# TIDA-01592_Power_Supply1.net
KiCad netlist of a schematic drawn in Altium Designer
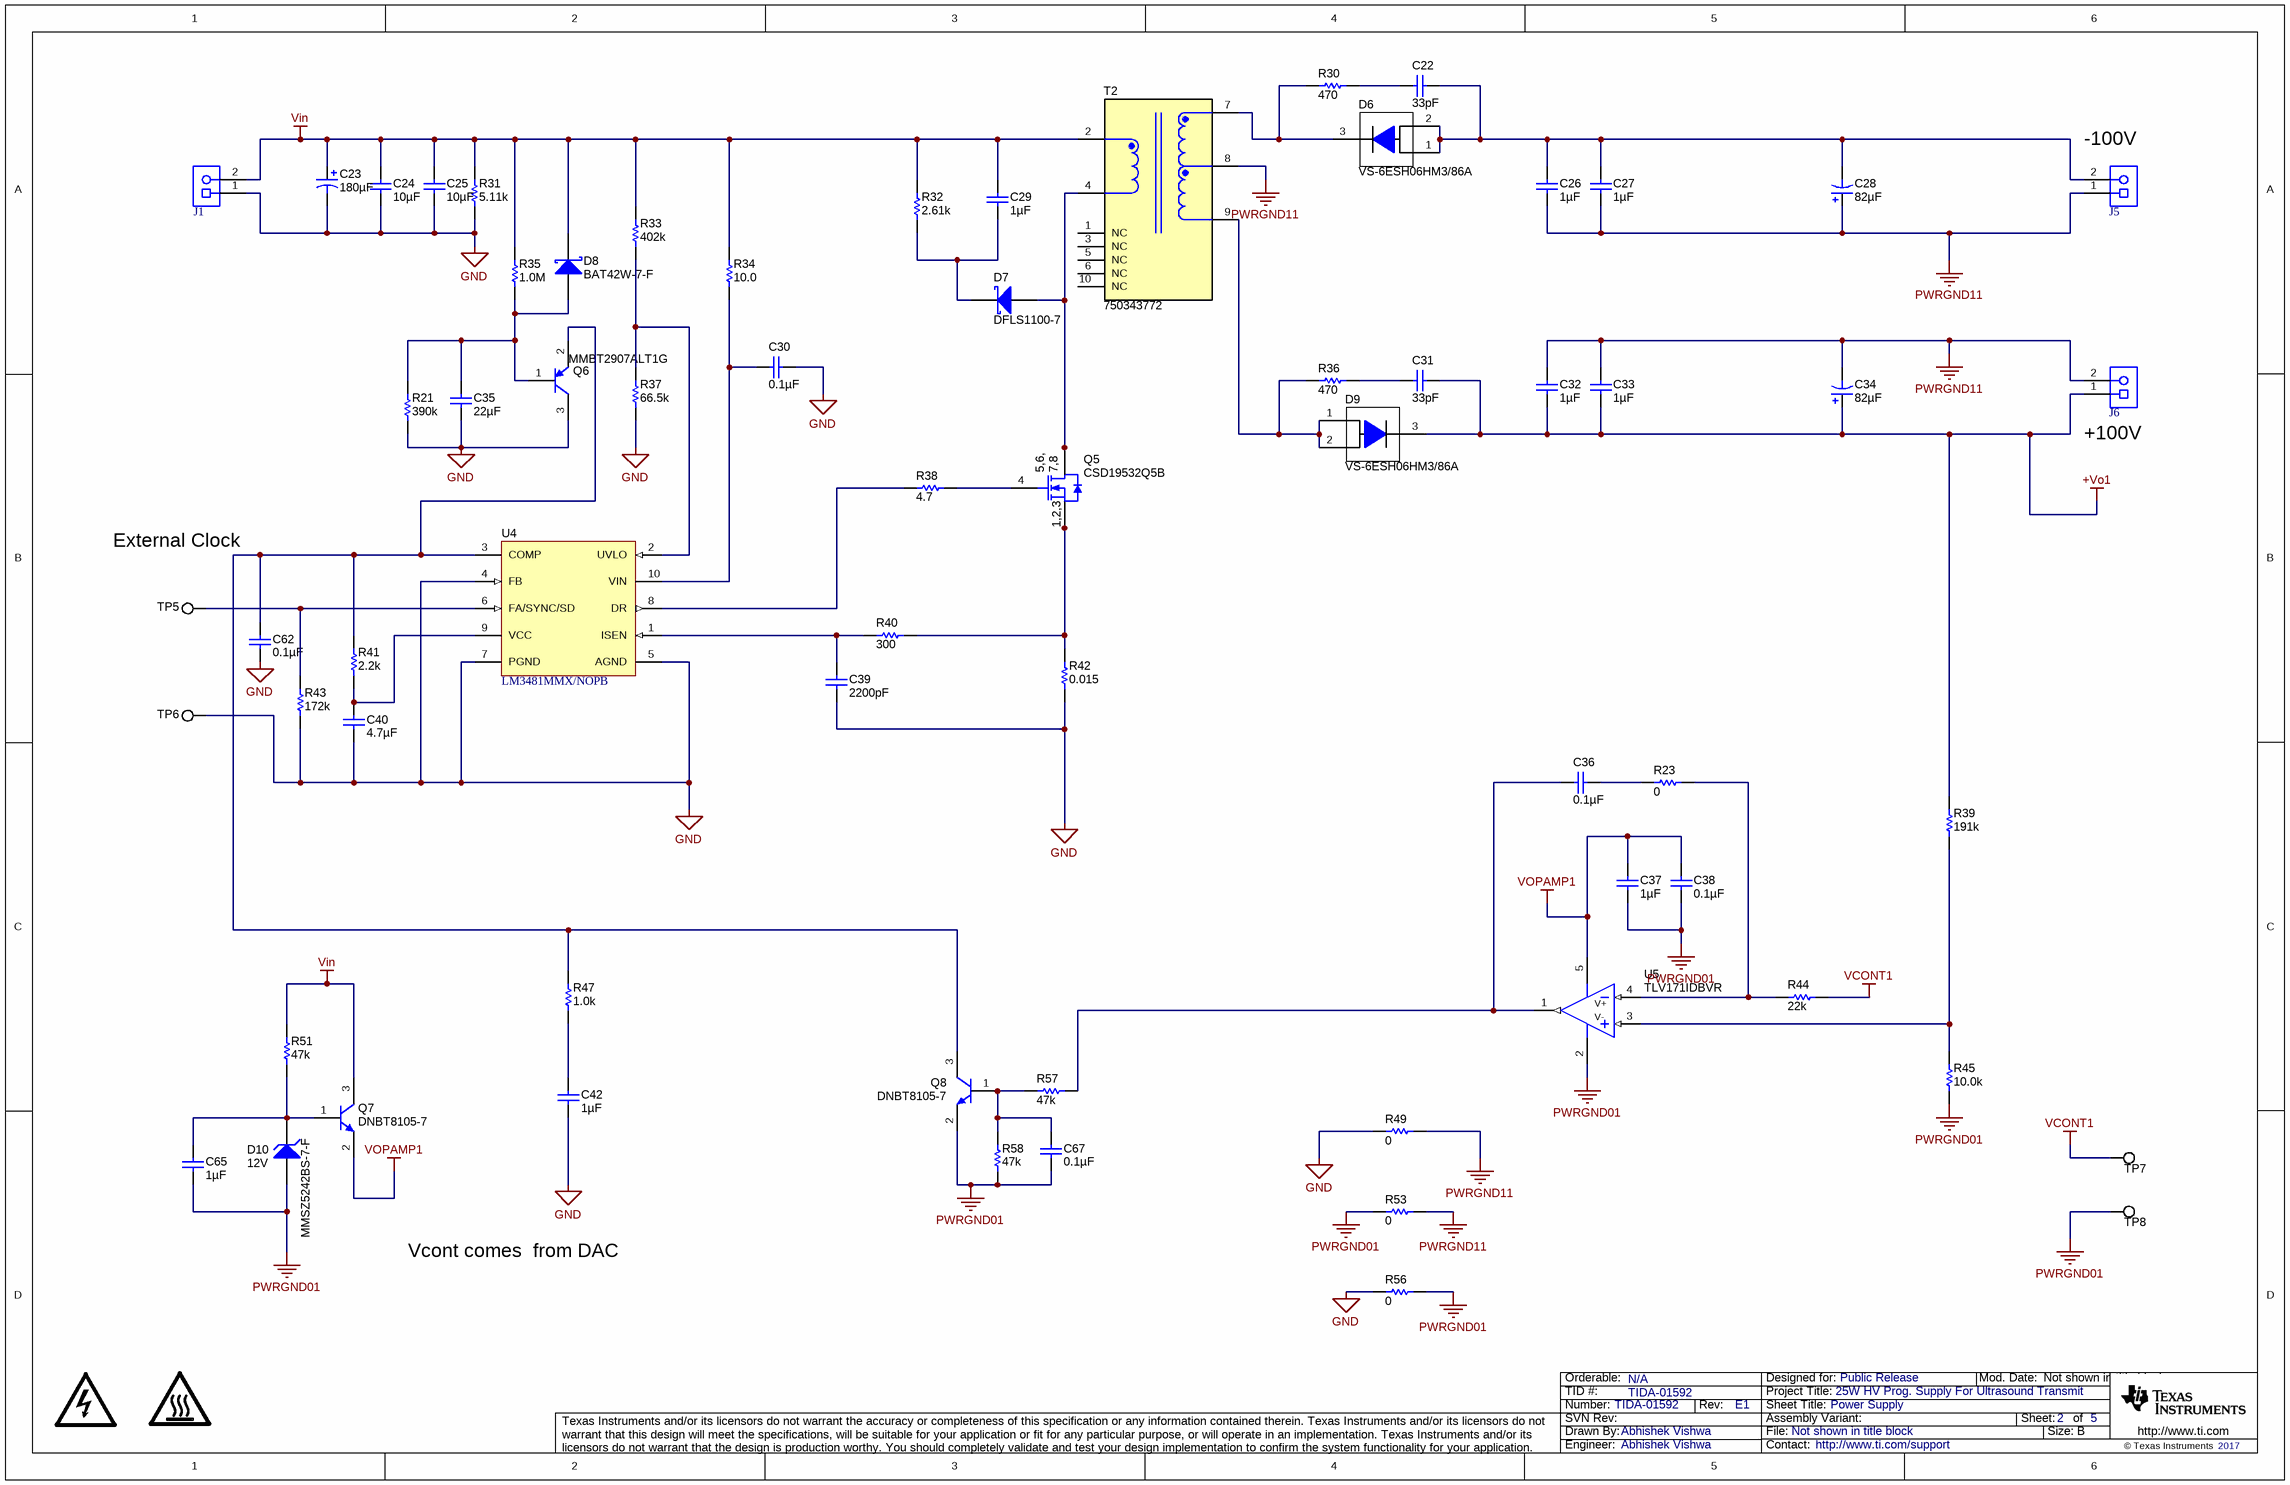
[diagram p0: TIDA-01592_Power Supply1.SchDoc]

(export (version "E")
  (design (tool "Eeschema 10.0.6"))
  (components
    (comp (ref "C22")
      (value "12067A330JAT2A")
      (footprint "1206")
      (description "CAP, CERM, 33 pF, 500 V,+/- 5%, C0G/NP0, 1206")
      (fields
        (field (name "VALUEDISPLAYED") "33pF")
        (field (name "MANUFACTURER") "AVX")
        (field (name "PUBLISHER") "Texas Instruments")
      )
      (libsource (lib "Capacitor_Ceramic") (part "12067A330JAT2A"))
    )
    (comp (ref "C23")
      (value "35TXW180MEFC6.3X25")
      (footprint "FC_630x1120")
      (description "CAP, AL, 180 µF, 35 V, +/- 20%, TH")
      (fields
        (field (name "VALUEDISPLAYED") "180µF")
        (field (name "MANUFACTURER") "Rubycon")
        (field (name "PUBLISHER") "Texas Instruments")
      )
      (libsource (lib "Capacitor_Aluminum") (part "EEU-FC1V470"))
    )
    (comp (ref "C24")
      (value "GRM31CR61H106KA12L")
      (footprint "1206_180")
      (description "CAP, CERM, 10 µF, 50 V,+/- 10%, X5R, 1206")
      (fields
        (field (name "VALUEDISPLAYED") "10µF")
        (field (name "MANUFACTURER") "MuRata")
        (field (name "PUBLISHER") "Texas Instruments")
      )
      (libsource (lib "Capacitor_Ceramic") (part "GRM31CR61H106KA12L"))
    )
    (comp (ref "C25")
      (value "GRM31CR61H106KA12L")
      (footprint "1206_180")
      (description "CAP, CERM, 10 µF, 50 V,+/- 10%, X5R, 1206")
      (fields
        (field (name "VALUEDISPLAYED") "10µF")
        (field (name "MANUFACTURER") "MuRata")
        (field (name "PUBLISHER") "Texas Instruments")
      )
      (libsource (lib "Capacitor_Ceramic") (part "GRM31CR61H106KA12L"))
    )
    (comp (ref "C26")
      (value "C4532X7T2E105M250KE")
      (footprint "1812_180")
      (description "CAP, CERM, 1 µF, 250 V,+/- 20%, X7T, 1812")
      (fields
        (field (name "VALUEDISPLAYED") "1µF")
        (field (name "MANUFACTURER") "TDK Corporation")
        (field (name "PUBLISHER") "Texas Instruments")
      )
      (libsource (lib "Capacitor_Ceramic") (part "C4532X7R1H105K160KA"))
    )
    (comp (ref "C27")
      (value "C4532X7T2E105M250KE")
      (footprint "1812_180")
      (description "CAP, CERM, 1 µF, 250 V,+/- 20%, X7T, 1812")
      (fields
        (field (name "VALUEDISPLAYED") "1µF")
        (field (name "MANUFACTURER") "TDK Corporation")
        (field (name "PUBLISHER") "Texas Instruments")
      )
      (libsource (lib "Capacitor_Ceramic") (part "C4532X7R1H105K160KA"))
    )
    (comp (ref "C28")
      (value "UCY2C820MPD9")
      (footprint "NHG_1000x2000")
      (description "CAP, AL, 82 µF, 160 V, +/- 20%, TH")
      (fields
        (field (name "VALUEDISPLAYED") "82µF")
        (field (name "MANUFACTURER") "Nichicon")
        (field (name "PUBLISHER") "Texas Instruments")
      )
      (libsource (lib "Capacitor_Aluminum") (part "ECA-2AHG101"))
    )
    (comp (ref "C29")
      (value "GRM31CR72A105KA01L")
      (footprint "1206_180")
      (description "CAP, CERM, 1 µF, 100 V,+/- 10%, X7R, 1206")
      (fields
        (field (name "VALUEDISPLAYED") "1µF")
        (field (name "MANUFACTURER") "MuRata")
        (field (name "PUBLISHER") "Texas Instruments")
      )
      (libsource (lib "Capacitor_Ceramic") (part "GRM31CR72A105KA01L"))
    )
    (comp (ref "C30")
      (value "GRM188R71H104KA93D")
      (footprint "0603")
      (description "CAP, CERM, 0.1 µF, 50 V,+/- 10%, X7R, 0603")
      (fields
        (field (name "VALUEDISPLAYED") "0.1µF")
        (field (name "MANUFACTURER") "MuRata")
        (field (name "PUBLISHER") "Texas Instruments")
      )
      (libsource (lib "Capacitor_Ceramic") (part "GRM188R71H104KA93D"))
    )
    (comp (ref "C31")
      (value "12067A330JAT2A")
      (footprint "1206")
      (description "CAP, CERM, 33 pF, 500 V,+/- 5%, C0G/NP0, 1206")
      (fields
        (field (name "VALUEDISPLAYED") "33pF")
        (field (name "MANUFACTURER") "AVX")
        (field (name "PUBLISHER") "Texas Instruments")
      )
      (libsource (lib "Capacitor_Ceramic") (part "12067A330JAT2A"))
    )
    (comp (ref "C32")
      (value "C4532X7T2E105M250KE")
      (footprint "1812_180")
      (description "CAP, CERM, 1 µF, 250 V,+/- 20%, X7T, 1812")
      (fields
        (field (name "VALUEDISPLAYED") "1µF")
        (field (name "MANUFACTURER") "TDK Corporation")
        (field (name "PUBLISHER") "Texas Instruments")
      )
      (libsource (lib "Capacitor_Ceramic") (part "C4532X7R1H105K160KA"))
    )
    (comp (ref "C33")
      (value "C4532X7T2E105M250KE")
      (footprint "1812_180")
      (description "CAP, CERM, 1 µF, 250 V,+/- 20%, X7T, 1812")
      (fields
        (field (name "VALUEDISPLAYED") "1µF")
        (field (name "MANUFACTURER") "TDK Corporation")
        (field (name "PUBLISHER") "Texas Instruments")
      )
      (libsource (lib "Capacitor_Ceramic") (part "C4532X7R1H105K160KA"))
    )
    (comp (ref "C34")
      (value "UCY2C820MPD9")
      (footprint "NHG_1000x2000")
      (description "CAP, AL, 82 µF, 160 V, +/- 20%, TH")
      (fields
        (field (name "VALUEDISPLAYED") "82µF")
        (field (name "MANUFACTURER") "Nichicon")
        (field (name "PUBLISHER") "Texas Instruments")
      )
      (libsource (lib "Capacitor_Aluminum") (part "ECA-2AHG101"))
    )
    (comp (ref "C35")
      (value "C2012X5R1V226M125AC")
      (footprint "0805_HV1")
      (description "CAP, CERM, 22 µF, 35 V,+/- 20%, X5R, 0805")
      (fields
        (field (name "VALUEDISPLAYED") "22µF")
        (field (name "MANUFACTURER") "TDK Corporation")
        (field (name "PUBLISHER") "Texas Instruments")
      )
      (libsource (lib "Capacitor_Ceramic") (part "GRM21BC81C226ME44L"))
    )
    (comp (ref "C36")
      (value "GRM188R71H104KA93D")
      (footprint "0603")
      (description "CAP, CERM, 0.1 µF, 50 V,+/- 10%, X7R, 0603")
      (fields
        (field (name "VALUEDISPLAYED") "0.1µF")
        (field (name "MANUFACTURER") "MuRata")
        (field (name "PUBLISHER") "Texas Instruments")
      )
      (libsource (lib "Capacitor_Ceramic") (part "GRM188R71H104KA93D"))
    )
    (comp (ref "C37")
      (value "UMK107AB7105KA-T")
      (footprint "0603")
      (description "CAP, CERM, 1 µF, 50 V,+/- 10%, X7R, 0603")
      (fields
        (field (name "VALUEDISPLAYED") "1µF")
        (field (name "MANUFACTURER") "Taiyo Yuden")
        (field (name "PUBLISHER") "Texas Instruments")
      )
      (libsource (lib "Capacitor_Ceramic") (part "UMK107AB7105KA-T"))
    )
    (comp (ref "C38")
      (value "GRM188R71H104KA93D")
      (footprint "0603")
      (description "CAP, CERM, 0.1 µF, 50 V,+/- 10%, X7R, 0603")
      (fields
        (field (name "VALUEDISPLAYED") "0.1µF")
        (field (name "MANUFACTURER") "MuRata")
        (field (name "PUBLISHER") "Texas Instruments")
      )
      (libsource (lib "Capacitor_Ceramic") (part "GRM188R71H104KA93D"))
    )
    (comp (ref "C39")
      (value "GRM155R61H222KA01D")
      (footprint "0402")
      (description "CAP, CERM, 2200 pF, 50 V,+/- 10%, X5R, 0402")
      (fields
        (field (name "VALUEDISPLAYED") "2200pF")
        (field (name "MANUFACTURER") "MuRata")
        (field (name "PUBLISHER") "Texas Instruments")
      )
      (libsource (lib "Capacitor_Ceramic") (part "GRM155R61H222KA01D"))
    )
    (comp (ref "C40")
      (value "0603ZD475KAT2A")
      (footprint "0603")
      (description "CAP, CERM, 4.7 µF, 10 V,+/- 10%, X5R, 0603")
      (fields
        (field (name "VALUEDISPLAYED") "4.7µF")
        (field (name "MANUFACTURER") "AVX")
        (field (name "PUBLISHER") "Texas Instruments")
      )
      (libsource (lib "Capacitor_Ceramic") (part "0603ZD475KAT2A"))
    )
    (comp (ref "C42")
      (value "C0603C105K3RACTU")
      (footprint "0603")
      (description "CAP, CERM, 1 µF, 25 V,+/- 10%, X7R, 0603")
      (fields
        (field (name "VALUEDISPLAYED") "1µF")
        (field (name "MANUFACTURER") "Kemet")
        (field (name "PUBLISHER") "Texas Instruments")
      )
      (libsource (lib "Capacitor_Ceramic") (part "C0603C105K3RACTU"))
    )
    (comp (ref "C62")
      (value "GRM188R71H104KA93D")
      (footprint "0603")
      (description "CAP, CERM, 0.1 µF, 50 V,+/- 10%, X7R, 0603")
      (fields
        (field (name "VALUEDISPLAYED") "0.1µF")
        (field (name "MANUFACTURER") "MuRata")
        (field (name "PUBLISHER") "Texas Instruments")
      )
      (libsource (lib "Capacitor_Ceramic") (part "GRM188R71H104KA93D"))
    )
    (comp (ref "C65")
      (value "C0603C105K3RACTU")
      (footprint "0603")
      (description "CAP, CERM, 1 µF, 25 V,+/- 10%, X7R, 0603")
      (fields
        (field (name "VALUEDISPLAYED") "1µF")
        (field (name "MANUFACTURER") "Kemet")
        (field (name "PUBLISHER") "Texas Instruments")
      )
      (libsource (lib "Capacitor_Ceramic") (part "C0603C105K3RACTU"))
    )
    (comp (ref "C67")
      (value "GRM188R71H104KA93D")
      (footprint "0603")
      (description "CAP, CERM, 0.1 µF, 50 V,+/- 10%, X7R, 0603")
      (fields
        (field (name "VALUEDISPLAYED") "0.1µF")
        (field (name "MANUFACTURER") "MuRata")
        (field (name "PUBLISHER") "Texas Instruments")
      )
      (libsource (lib "Capacitor_Ceramic") (part "GRM188R71H104KA93D"))
    )
    (comp (ref "D6")
      (value "VS-6ESH06HM3/86A")
      (footprint "TO-277A")
      (description "Diode, Hyperfast, 600 V, 6 A, AEC-Q101, TO-277A")
      (fields
        (field (name "MANUFACTURER") "Vishay-Semiconductor")
        (field (name "SYMBOLCREATOR") "a0412235")
        (field (name "PUBLISHER") "Texas Instruments")
      )
      (libsource (lib "Diode") (part "VS-6ESH06HM3/86A"))
    )
    (comp (ref "D7")
      (value "DFLS1100-7")
      (footprint "PowerDI123")
      (description "Diode, Schottky, 100 V, 1 A, PowerDI123")
      (fields (field (name "MANUFACTURER") "Diodes Inc.") (field (name "PUBLISHER") "Texas Instruments"))
      (libsource (lib "Diode") (part "DFLS1100-7"))
    )
    (comp (ref "D8")
      (value "BAT42W-7-F")
      (footprint "SOD-123")
      (description "Diode, Schottky, 30 V, 0.2 A, SOD-123")
      (fields (field (name "MANUFACTURER") "Diodes Inc.") (field (name "PUBLISHER") "Texas Instruments"))
      (libsource (lib "Diode") (part "BAT42W-7-F"))
    )
    (comp (ref "D9")
      (value "VS-6ESH06HM3/86A")
      (footprint "TO-277A")
      (description "Diode, Hyperfast, 600 V, 6 A, AEC-Q101, TO-277A")
      (fields
        (field (name "MANUFACTURER") "Vishay-Semiconductor")
        (field (name "SYMBOLCREATOR") "a0412235")
        (field (name "PUBLISHER") "Texas Instruments")
      )
      (libsource (lib "") (part "VS-6ESH06HM3/86A_1"))
    )
    (comp (ref "D10")
      (value "MMSZ5242BS-7-F")
      (footprint "SOD-323")
      (description "Diode, Zener, 12 V, 200 mW, SOD-323")
      (fields
        (field (name "ALTIUM_VALUE") "12V")
        (field (name "MANUFACTURER") "Diodes Inc.")
        (field (name "SYMBOLCREATOR") "a0412235")
        (field (name "PUBLISHER") "Texas Instruments")
      )
      (libsource (lib "ZenerDiodes") (part "MMSZ5242BS-7-F"))
    )
    (comp (ref "J1")
      (value "1727010")
      (footprint "PhoenixConact_1727010")
      (description "Conn Term Block, 2POS, 3.81mm, TH")
      (fields
        (field (name "MANUFACTURER") "Phoenix Contact")
        (field (name "SYMBOLCREATOR") "a0412235")
        (field (name "PUBLISHER") "Texas Instruments")
      )
      (libsource (lib "Connectors_Phoenix_Contact") (part "1727010"))
    )
    (comp (ref "J5")
      (value "1727010")
      (footprint "PhoenixConact_1727010")
      (description "Conn Term Block, 2POS, 3.81mm, TH")
      (fields
        (field (name "MANUFACTURER") "Phoenix Contact")
        (field (name "SYMBOLCREATOR") "a0412235")
        (field (name "PUBLISHER") "Texas Instruments")
      )
      (libsource (lib "") (part "1727010_1"))
    )
    (comp (ref "J6")
      (value "1727010")
      (footprint "PhoenixConact_1727010")
      (description "Conn Term Block, 2POS, 3.81mm, TH")
      (fields
        (field (name "MANUFACTURER") "Phoenix Contact")
        (field (name "SYMBOLCREATOR") "a0412235")
        (field (name "PUBLISHER") "Texas Instruments")
      )
      (libsource (lib "") (part "1727010_1"))
    )
    (comp (ref "Q5")
      (value "CSD19532Q5B")
      (footprint "DNK0008A")
      (description "MOSFET, N-CH, 100 V, 17 A, DNK0008A (VSON-CLIP-8)")
      (fields
        (field (name "MANUFACTURER") "Texas Instruments")
        (field (name "PUBLISHER") "Texas Instruments")
      )
      (libsource (lib "FETs") (part "CSD19532Q5B"))
    )
    (comp (ref "Q6")
      (value "MMBT2907ALT1G")
      (footprint "SOT-23")
      (description "Transistor, PNP, 60 V, 0.6 A, SOT-23")
      (fields (field (name "MANUFACTURER") "ON Semiconductor") (field (name "PUBLISHER") "Texas Instruments"))
      (libsource (lib "Bipolar_Transistor") (part "MMBT2907ALT1G, ON Semiconductor"))
    )
    (comp (ref "Q7")
      (value "DNBT8105-7")
      (footprint "SOT-23")
      (description "Transistor, NPN, 60 V, 1 A, AEC-Q101, SOT-23")
      (fields (field (name "MANUFACTURER") "Diodes Inc.") (field (name "PUBLISHER") "Texas Instruments"))
      (libsource (lib "Bipolar_Transistor") (part "DNBT8105-7, Diodes Inc."))
    )
    (comp (ref "Q8")
      (value "DNBT8105-7")
      (footprint "SOT-23")
      (description "Transistor, NPN, 60 V, 1 A, AEC-Q101, SOT-23")
      (fields (field (name "MANUFACTURER") "Diodes Inc.") (field (name "PUBLISHER") "Texas Instruments"))
      (libsource (lib "Bipolar_Transistor") (part "DNBT8105-7, Diodes Inc."))
    )
    (comp (ref "R21")
      (value "CRCW0603390KJNEA")
      (footprint "0603")
      (description "RES, 390 k, 5%, 0.1 W, 0603")
      (fields
        (field (name "VALUEDISPLAYED") "390k")
        (field (name "MANUFACTURER") "Vishay-Dale")
        (field (name "PUBLISHER") "Texas Instruments")
      )
      (libsource (lib "Resistor_0603") (part "CRCW0603390KJNEA"))
    )
    (comp (ref "R23")
      (value "CRCW04020000Z0ED")
      (footprint "0402")
      (description "RES, 0, 5%, 0.063 W, 0402")
      (fields
        (field (name "VALUEDISPLAYED") "0")
        (field (name "MANUFACTURER") "Vishay-Dale")
        (field (name "PUBLISHER") "Texas Instruments")
      )
      (libsource (lib "Resistor_0402") (part "CRCW04020000Z0ED"))
    )
    (comp (ref "R30")
      (value "CRCW1206470RJNEA")
      (footprint "1206")
      (description "RES, 470, 5%, 0.25 W, 1206")
      (fields
        (field (name "VALUEDISPLAYED") "470")
        (field (name "MANUFACTURER") "Vishay-Dale")
        (field (name "PUBLISHER") "Texas Instruments")
      )
      (libsource (lib "Resistor_1206") (part "CRCW1206470RJNEA"))
    )
    (comp (ref "R31")
      (value "TNPW06035K11BEEA")
      (footprint "TNPW0603")
      (description "RES, 5.11 k, 0.1%, 0.1 W, AEC-Q200 Grade 1, 0603")
      (fields
        (field (name "VALUEDISPLAYED") "5.11k")
        (field (name "MANUFACTURER") "Vishay-Dale")
        (field (name "PUBLISHER") "Texas Instruments")
      )
      (libsource (lib "Resistor_0603") (part "TNPW06035K11BEEA"))
    )
    (comp (ref "R32")
      (value "CRCW20102K61FKEF")
      (footprint "2010")
      (description "RES, 2.61 k, 1%, 0.75 W, AEC-Q200 Grade 0, 2010")
      (fields
        (field (name "VALUEDISPLAYED") "2.61k")
        (field (name "MANUFACTURER") "Vishay-Dale")
        (field (name "PUBLISHER") "Texas Instruments")
      )
      (libsource (lib "Resistor_2010") (part "CRCW20102K61FKEF"))
    )
    (comp (ref "R33")
      (value "CRCW0603402KFKEA")
      (footprint "0603")
      (description "RES, 402 k, 1%, 0.1 W, 0603")
      (fields
        (field (name "VALUEDISPLAYED") "402k")
        (field (name "MANUFACTURER") "Vishay-Dale")
        (field (name "PUBLISHER") "Texas Instruments")
      )
      (libsource (lib "Resistor_0603") (part "CRCW0603402KFKEA"))
    )
    (comp (ref "R34")
      (value "CRCW060310R0FKEAHP")
      (footprint "0603")
      (description "RES, 10.0, 1%, 0.25 W, 0603")
      (fields
        (field (name "R4") "10.0")
        (field (name "MANUFACTURER") "Vishay-Dale")
        (field (name "PUBLISHER") "Texas Instruments")
      )
      (libsource (lib "Resistor_0603") (part "CRCW060310R0FKEAHP"))
    )
    (comp (ref "R35")
      (value "CRCW06031M00JNEA")
      (footprint "0603")
      (description "RES, 1.0 M, 5%, 0.1 W, 0603")
      (fields
        (field (name "VALUEDISPLAYED") "1.0M")
        (field (name "MANUFACTURER") "Vishay-Dale")
        (field (name "PUBLISHER") "Texas Instruments")
      )
      (libsource (lib "Resistor_0603") (part "CRCW06031M00JNEA"))
    )
    (comp (ref "R36")
      (value "CRCW1206470RJNEA")
      (footprint "1206")
      (description "RES, 470, 5%, 0.25 W, 1206")
      (fields
        (field (name "VALUEDISPLAYED") "470")
        (field (name "MANUFACTURER") "Vishay-Dale")
        (field (name "PUBLISHER") "Texas Instruments")
      )
      (libsource (lib "Resistor_1206") (part "CRCW1206470RJNEA"))
    )
    (comp (ref "R37")
      (value "CRCW060366K5FKEA")
      (footprint "0603")
      (description "RES, 66.5 k, 1%, 0.1 W, 0603")
      (fields
        (field (name "VALUEDISPLAYED") "66.5k")
        (field (name "MANUFACTURER") "Vishay-Dale")
        (field (name "PUBLISHER") "Texas Instruments")
      )
      (libsource (lib "Resistor_0603") (part "CRCW060366K5FKEA"))
    )
    (comp (ref "R38")
      (value "CRCW06034R70JNEA")
      (footprint "0603")
      (description "RES, 4.7, 5%, 0.1 W, 0603")
      (fields
        (field (name "VALUEDISPLAYED") "4.7")
        (field (name "MANUFACTURER") "Vishay-Dale")
        (field (name "PUBLISHER") "Texas Instruments")
      )
      (libsource (lib "Resistor_0603") (part "CRCW06034R70JNEA"))
    )
    (comp (ref "R39")
      (value "CRCW0603191KFKEA")
      (footprint "0603")
      (description "RES, 191 k, 1%, 0.1 W, 0603")
      (fields
        (field (name "VALUEDISPLAYED") "191k")
        (field (name "MANUFACTURER") "Vishay-Dale")
        (field (name "PUBLISHER") "Texas Instruments")
      )
      (libsource (lib "Resistor_0603") (part "CRCW0603191KFKEA"))
    )
    (comp (ref "R40")
      (value "CRCW0603300RJNEA")
      (footprint "0603")
      (description "RES, 300, 5%, 0.1 W, 0603")
      (fields
        (field (name "VALUEDISPLAYED") "300")
        (field (name "MANUFACTURER") "Vishay-Dale")
        (field (name "PUBLISHER") "Texas Instruments")
      )
      (libsource (lib "Resistor_0603") (part "CRCW0603300RJNEA"))
    )
    (comp (ref "R41")
      (value "ERJ-3GEYJ222V")
      (footprint "0603")
      (description "RES, 2.2 k, 5%, 0.1 W, AEC-Q200 Grade 0, 0603")
      (fields
        (field (name "VALUEDISPLAYED") "2.2k")
        (field (name "MANUFACTURER") "Panasonic")
        (field (name "PUBLISHER") "Texas Instruments")
      )
      (libsource (lib "Resistor_0603") (part "ERJ-3GEYJ222V"))
    )
    (comp (ref "R42")
      (value "WSL2010R0150FEA18")
      (footprint "2010")
      (description "RES, 0.015, 1%, 1 W, 2010")
      (fields
        (field (name "VALUEDISPLAYED") "0.015")
        (field (name "MANUFACTURER") "Vishay-Dale")
        (field (name "PUBLISHER") "Texas Instruments")
      )
      (libsource (lib "Resistor_2010") (part "WSL2010R0150FEA18"))
    )
    (comp (ref "R43")
      (value "RT0603DRE07172KL")
      (footprint "0603")
      (description "RES, 172 k, 0.5%, 0.1 W, 0603")
      (fields
        (field (name "VALUEDISPLAYED") "172k")
        (field (name "MANUFACTURER") "Yageo America")
        (field (name "PUBLISHER") "Texas Instruments")
      )
      (libsource (lib "Resistor_0603") (part "RT0603DRE07172KL"))
    )
    (comp (ref "R44")
      (value "CRCW060322K0JNEA")
      (footprint "0603")
      (description "RES, 22 k, 5%, 0.1 W, 0603")
      (fields
        (field (name "VALUEDISPLAYED") "22k")
        (field (name "MANUFACTURER") "Vishay-Dale")
        (field (name "PUBLISHER") "Texas Instruments")
      )
      (libsource (lib "Resistor_0603") (part "CRCW060322K0JNEA"))
    )
    (comp (ref "R45")
      (value "CRCW060310K0FKEA")
      (footprint "0603")
      (description "RES, 10.0 k, 1%, 0.1 W, 0603")
      (fields
        (field (name "VALUEDISPLAYED") "10.0k")
        (field (name "MANUFACTURER") "Vishay-Dale")
        (field (name "PUBLISHER") "Texas Instruments")
      )
      (libsource (lib "Resistor_0603") (part "CRCW060310K0FKEA"))
    )
    (comp (ref "R47")
      (value "CRCW06031K00JNEA")
      (footprint "0603")
      (description "RES, 1.0 k, 5%, 0.1 W, 0603")
      (fields
        (field (name "VALUEDISPLAYED") "1.0k")
        (field (name "MANUFACTURER") "Vishay-Dale")
        (field (name "PUBLISHER") "Texas Instruments")
      )
      (libsource (lib "Resistor_0603") (part "CRCW06031K00JNEA"))
    )
    (comp (ref "R49")
      (value "CRCW20100000Z0EF")
      (footprint "2010L")
      (description "RES, 0, 5%, 0.75 W, AEC-Q200 Grade 0, 2010")
      (fields
        (field (name "VALUEDISPLAYED") "0")
        (field (name "MANUFACTURER") "Vishay-Dale")
        (field (name "PUBLISHER") "Texas Instruments")
      )
      (libsource (lib "Resistor_2010") (part "CRCW20100000Z0EF"))
    )
    (comp (ref "R51")
      (value "CRCW120647K0JNEA")
      (footprint "1206")
      (description "RES, 47 k, 5%, 0.25 W, 1206")
      (fields
        (field (name "VALUEDISPLAYED") "47k")
        (field (name "MANUFACTURER") "Vishay-Dale")
        (field (name "PUBLISHER") "Texas Instruments")
      )
      (libsource (lib "Resistor_1206") (part "CRCW120647K0JNEA"))
    )
    (comp (ref "R53")
      (value "CRCW20100000Z0EF")
      (footprint "2010L")
      (description "RES, 0, 5%, 0.75 W, AEC-Q200 Grade 0, 2010")
      (fields
        (field (name "VALUEDISPLAYED") "0")
        (field (name "MANUFACTURER") "Vishay-Dale")
        (field (name "PUBLISHER") "Texas Instruments")
      )
      (libsource (lib "Resistor_2010") (part "CRCW20100000Z0EF"))
    )
    (comp (ref "R56")
      (value "CRCW20100000Z0EF")
      (footprint "2010L")
      (description "RES, 0, 5%, 0.75 W, AEC-Q200 Grade 0, 2010")
      (fields
        (field (name "VALUEDISPLAYED") "0")
        (field (name "MANUFACTURER") "Vishay-Dale")
        (field (name "PUBLISHER") "Texas Instruments")
      )
      (libsource (lib "Resistor_2010") (part "CRCW20100000Z0EF"))
    )
    (comp (ref "R57")
      (value "RC0603JR-0747KL")
      (footprint "0603")
      (description "RES, 47 k, 5%, 0.1 W, 0603")
      (fields
        (field (name "VALUEDISPLAYED") "47k")
        (field (name "MANUFACTURER") "Yageo America")
        (field (name "PUBLISHER") "Texas Instruments")
      )
      (libsource (lib "Resistor_0603") (part "RC0603JR-0747KL"))
    )
    (comp (ref "R58")
      (value "RC0603JR-0747KL")
      (footprint "0603")
      (description "RES, 47 k, 5%, 0.1 W, 0603")
      (fields
        (field (name "VALUEDISPLAYED") "47k")
        (field (name "MANUFACTURER") "Yageo America")
        (field (name "PUBLISHER") "Texas Instruments")
      )
      (libsource (lib "Resistor_0603") (part "RC0603JR-0747KL"))
    )
    (comp (ref "T2")
      (value "750343772")
      (footprint "Wurth_EE16_7_5_5278")
      (description "Transformer, 13 uH, TH")
      (fields (field (name "MANUFACTURER") "Wurth Elektronik"))
      (libsource (lib "Altium Vault - TI") (part "Wurth_750343772"))
    )
    (comp (ref "TP5")
      (value "5002")
      (footprint "Keystone5002")
      (description "Test Point, Miniature, White, TH")
      (fields (field (name "MANUFACTURER") "Keystone") (field (name "PUBLISHER") "Texas Instruments"))
      (libsource (lib "Connectors_Keystone") (part "5002"))
    )
    (comp (ref "TP6")
      (value "5002")
      (footprint "Keystone5002")
      (description "Test Point, Miniature, White, TH")
      (fields (field (name "MANUFACTURER") "Keystone") (field (name "PUBLISHER") "Texas Instruments"))
      (libsource (lib "Connectors_Keystone") (part "5002"))
    )
    (comp (ref "TP7")
      (value "5002")
      (footprint "Keystone5002")
      (description "Test Point, Miniature, White, TH")
      (fields (field (name "MANUFACTURER") "Keystone") (field (name "PUBLISHER") "Texas Instruments"))
      (libsource (lib "Connectors_Keystone") (part "5002"))
    )
    (comp (ref "TP8")
      (value "5002")
      (footprint "Keystone5002")
      (description "Test Point, Miniature, White, TH")
      (fields (field (name "MANUFACTURER") "Keystone") (field (name "PUBLISHER") "Texas Instruments"))
      (libsource (lib "Connectors_Keystone") (part "5002"))
    )
    (comp (ref "U4")
      (value "LM3481MMX/NOPB")
      (footprint "MUB10A_N")
      (description "High Efficiency Low-Side N-Channel Controller for Switching Regulators, 10-pin MSOP, Pb-Free")
      (fields (field (name "MANUFACTURER") "Texas Instruments") (field (name "PUBLISHER") "Altium Limited"))
      (libsource (lib "NSC MiscPower") (part "LM3481MMX/NOPB"))
    )
    (comp (ref "U5")
      (value "TLV171IDBVR")
      (footprint "DBV0005A_N")
      (description "36V, Low-Power, RRO, General-Purpose Operational Amplifier, DBV0005A (SOT-23-5)")
      (fields
        (field (name "ALTERNATE PARTNUMBER") "TLV171IDBVT")
        (field (name "MANUFACTURER") "Texas Instruments")
        (field (name "PUBLISHER") "Texas Instruments")
      )
      (libsource (lib "TI_Pre_Release1") (part "TLV171IDBVR"))
    )
  )
  (nets
    (net (code "1") (name "+Vo1") (class "Default")
      (node (ref "C31") (pin "1") (pinfunction "1_1") (pintype "passive"))
      (node (ref "C32") (pin "2") (pinfunction "2_2") (pintype "passive"))
      (node (ref "C33") (pin "2") (pinfunction "2_2") (pintype "passive"))
      (node (ref "C34") (pin "1") (pinfunction "+_1") (pintype "passive"))
      (node (ref "D9") (pin "3") (pinfunction "K_3") (pintype "passive"))
      (node (ref "J6") (pin "1") (pinfunction "1_1") (pintype "passive"))
      (node (ref "R39") (pin "2") (pinfunction "2_2") (pintype "passive"))
    )
    (net (code "2") (name "GND") (class "Default")
      (node (ref "C23") (pin "2") (pinfunction "-_2") (pintype "passive"))
      (node (ref "C24") (pin "2") (pinfunction "2_2") (pintype "passive"))
      (node (ref "C25") (pin "2") (pinfunction "2_2") (pintype "passive"))
      (node (ref "C30") (pin "1") (pinfunction "1_1") (pintype "passive"))
      (node (ref "C35") (pin "2") (pinfunction "2_2") (pintype "passive"))
      (node (ref "C39") (pin "2") (pinfunction "2_2") (pintype "passive"))
      (node (ref "C40") (pin "2") (pinfunction "2_2") (pintype "passive"))
      (node (ref "C42") (pin "2") (pinfunction "2_2") (pintype "passive"))
      (node (ref "C62") (pin "1") (pinfunction "1_1") (pintype "passive"))
      (node (ref "J1") (pin "1") (pinfunction "1_1") (pintype "passive"))
      (node (ref "Q6") (pin "3") (pinfunction "C_3") (pintype "passive"))
      (node (ref "R21") (pin "1") (pinfunction "1_1") (pintype "passive"))
      (node (ref "R31") (pin "1") (pinfunction "1_1") (pintype "passive"))
      (node (ref "R37") (pin "1") (pinfunction "1_1") (pintype "passive"))
      (node (ref "R42") (pin "1") (pinfunction "1_1") (pintype "passive"))
      (node (ref "R43") (pin "1") (pinfunction "1_1") (pintype "passive"))
      (node (ref "R49") (pin "1") (pinfunction "1_1") (pintype "passive"))
      (node (ref "R56") (pin "1") (pinfunction "1_1") (pintype "passive"))
      (node (ref "TP6") (pin "1") (pintype "passive"))
      (node (ref "U4") (pin "4") (pinfunction "FB_4") (pintype "input"))
      (node (ref "U4") (pin "5") (pinfunction "AGND_5") (pintype "power_in"))
      (node (ref "U4") (pin "7") (pinfunction "PGND_7") (pintype "power_in"))
    )
    (net (code "3") (name "Net-(C22-Pad2)") (class "Default")
      (node (ref "C22") (pin "2") (pinfunction "2_2") (pintype "passive"))
      (node (ref "R30") (pin "2") (pinfunction "2_2") (pintype "passive"))
    )
    (net (code "4") (name "Net-(C28--)") (class "Default")
      (node (ref "C22") (pin "1") (pinfunction "1_1") (pintype "passive"))
      (node (ref "C26") (pin "1") (pinfunction "1_1") (pintype "passive"))
      (node (ref "C27") (pin "1") (pinfunction "1_1") (pintype "passive"))
      (node (ref "C28") (pin "2") (pinfunction "-_2") (pintype "passive"))
      (node (ref "D6") (pin "1") (pinfunction "A_1") (pintype "passive"))
      (node (ref "D6") (pin "2") (pinfunction "A_2") (pintype "passive"))
      (node (ref "J5") (pin "2") (pinfunction "2_2") (pintype "passive"))
    )
    (net (code "5") (name "Net-(C31-Pad2)") (class "Default")
      (node (ref "C31") (pin "2") (pinfunction "2_2") (pintype "passive"))
      (node (ref "R36") (pin "2") (pinfunction "2_2") (pintype "passive"))
    )
    (net (code "6") (name "Net-(C36-Pad2)") (class "Default")
      (node (ref "C36") (pin "2") (pinfunction "2_2") (pintype "passive"))
      (node (ref "R23") (pin "1") (pinfunction "1_1") (pintype "passive"))
    )
    (net (code "7") (name "Net-(C42-Pad1)") (class "Default")
      (node (ref "C42") (pin "1") (pinfunction "1_1") (pintype "passive"))
      (node (ref "R47") (pin "1") (pinfunction "1_1") (pintype "passive"))
    )
    (net (code "8") (name "Net-(D6-K)") (class "Default")
      (node (ref "D6") (pin "3") (pinfunction "K_3") (pintype "passive"))
      (node (ref "R30") (pin "1") (pinfunction "1_1") (pintype "passive"))
      (node (ref "T2") (pin "7") (pinfunction "7_7") (pintype "passive"))
    )
    (net (code "9") (name "Net-(D7-A)") (class "Default")
      (node (ref "D7") (pin "2") (pinfunction "A_2") (pintype "passive"))
      (node (ref "Q5") (pin "5") (pinfunction "D_5") (pintype "passive"))
      (node (ref "Q5") (pin "6") (pinfunction "D_6") (pintype "passive"))
      (node (ref "Q5") (pin "7") (pinfunction "D_7") (pintype "passive"))
      (node (ref "Q5") (pin "8") (pinfunction "D_8") (pintype "passive"))
      (node (ref "Q5") (pin "9") (pinfunction "D_9") (pintype "passive"))
      (node (ref "T2") (pin "4") (pinfunction "4_4") (pintype "passive"))
    )
    (net (code "10") (name "Net-(D7-K)") (class "Default")
      (node (ref "C29") (pin "2") (pinfunction "2_2") (pintype "passive"))
      (node (ref "D7") (pin "1") (pinfunction "K_1") (pintype "passive"))
      (node (ref "R32") (pin "1") (pinfunction "1_1") (pintype "passive"))
    )
    (net (code "11") (name "Net-(D8-A)") (class "Default")
      (node (ref "C35") (pin "1") (pinfunction "1_1") (pintype "passive"))
      (node (ref "D8") (pin "2") (pinfunction "A_2") (pintype "passive"))
      (node (ref "Q6") (pin "1") (pinfunction "B_1") (pintype "passive"))
      (node (ref "R21") (pin "2") (pinfunction "2_2") (pintype "passive"))
      (node (ref "R35") (pin "1") (pinfunction "1_1") (pintype "passive"))
    )
    (net (code "12") (name "Net-(D9-A-Pad1)") (class "Default")
      (node (ref "D9") (pin "1") (pinfunction "A_1") (pintype "passive"))
      (node (ref "D9") (pin "2") (pinfunction "A_2") (pintype "passive"))
      (node (ref "R36") (pin "1") (pinfunction "1_1") (pintype "passive"))
      (node (ref "T2") (pin "9") (pinfunction "9_9") (pintype "passive"))
    )
    (net (code "13") (name "Net-(D10-K)") (class "Default")
      (node (ref "C65") (pin "1") (pinfunction "1_1") (pintype "passive"))
      (node (ref "D10") (pin "1") (pinfunction "K_1") (pintype "passive"))
      (node (ref "Q7") (pin "1") (pinfunction "B_1") (pintype "passive"))
      (node (ref "R51") (pin "1") (pinfunction "1_1") (pintype "passive"))
    )
    (net (code "14") (name "Net-(Q5-G)") (class "Default")
      (node (ref "Q5") (pin "4") (pinfunction "G_4") (pintype "passive"))
      (node (ref "R38") (pin "2") (pinfunction "2_2") (pintype "passive"))
    )
    (net (code "15") (name "Net-(Q5-S-Pad1)") (class "Default")
      (node (ref "Q5") (pin "1") (pinfunction "S_1") (pintype "passive"))
      (node (ref "Q5") (pin "2") (pinfunction "S_2") (pintype "passive"))
      (node (ref "Q5") (pin "3") (pinfunction "S_3") (pintype "passive"))
      (node (ref "R40") (pin "2") (pinfunction "2_2") (pintype "passive"))
      (node (ref "R42") (pin "2") (pinfunction "2_2") (pintype "passive"))
    )
    (net (code "16") (name "Net-(Q6-E)") (class "Default")
      (node (ref "C62") (pin "2") (pinfunction "2_2") (pintype "passive"))
      (node (ref "Q6") (pin "2") (pinfunction "E_2") (pintype "passive"))
      (node (ref "Q8") (pin "3") (pinfunction "C_3") (pintype "passive"))
      (node (ref "R41") (pin "1") (pinfunction "1_1") (pintype "passive"))
      (node (ref "R47") (pin "2") (pinfunction "2_2") (pintype "passive"))
      (node (ref "U4") (pin "3") (pinfunction "COMP_3") (pintype "passive"))
    )
    (net (code "17") (name "Net-(Q8-B)") (class "Default")
      (node (ref "C67") (pin "2") (pinfunction "2_2") (pintype "passive"))
      (node (ref "Q8") (pin "1") (pinfunction "B_1") (pintype "passive"))
      (node (ref "R57") (pin "2") (pinfunction "2_2") (pintype "passive"))
      (node (ref "R58") (pin "1") (pinfunction "1_1") (pintype "passive"))
    )
    (net (code "18") (name "Net-(U4-DR)") (class "Default")
      (node (ref "R38") (pin "1") (pinfunction "1_1") (pintype "passive"))
      (node (ref "U4") (pin "8") (pinfunction "DR_8") (pintype "output"))
    )
    (net (code "19") (name "Net-(U4-FA{slash}SYNC{slash}SD)") (class "Default")
      (node (ref "R43") (pin "2") (pinfunction "2_2") (pintype "passive"))
      (node (ref "TP5") (pin "1") (pintype "passive"))
      (node (ref "U4") (pin "6") (pinfunction "FA/SYNC/SD_6") (pintype "input"))
    )
    (net (code "20") (name "Net-(U4-ISEN)") (class "Default")
      (node (ref "C39") (pin "1") (pinfunction "1_1") (pintype "passive"))
      (node (ref "R40") (pin "1") (pinfunction "1_1") (pintype "passive"))
      (node (ref "U4") (pin "1") (pinfunction "ISEN_1") (pintype "input"))
    )
    (net (code "21") (name "Net-(U4-UVLO)") (class "Default")
      (node (ref "R33") (pin "1") (pinfunction "1_1") (pintype "passive"))
      (node (ref "R37") (pin "2") (pinfunction "2_2") (pintype "passive"))
      (node (ref "U4") (pin "2") (pinfunction "UVLO_2") (pintype "input"))
    )
    (net (code "22") (name "Net-(U4-VCC)") (class "Default")
      (node (ref "C40") (pin "1") (pinfunction "1_1") (pintype "passive"))
      (node (ref "R41") (pin "2") (pinfunction "2_2") (pintype "passive"))
      (node (ref "U4") (pin "9") (pinfunction "VCC_9") (pintype "power_in"))
    )
    (net (code "23") (name "Net-(U4-VIN)") (class "Default")
      (node (ref "C30") (pin "2") (pinfunction "2_2") (pintype "passive"))
      (node (ref "R34") (pin "2") (pinfunction "2_2") (pintype "passive"))
      (node (ref "U4") (pin "10") (pinfunction "VIN_10") (pintype "power_in"))
    )
    (net (code "24") (name "Net-(U5-IN+)") (class "Default")
      (node (ref "R39") (pin "1") (pinfunction "1_1") (pintype "passive"))
      (node (ref "R45") (pin "1") (pinfunction "1_1") (pintype "passive"))
      (node (ref "U5") (pin "3") (pinfunction "IN+_3") (pintype "input"))
    )
    (net (code "25") (name "Net-(U5-IN-)") (class "Default")
      (node (ref "R23") (pin "2") (pinfunction "2_2") (pintype "passive"))
      (node (ref "R44") (pin "1") (pinfunction "1_1") (pintype "passive"))
      (node (ref "U5") (pin "4") (pinfunction "IN-_4") (pintype "input"))
    )
    (net (code "26") (name "Net-(U5-OUT)") (class "Default")
      (node (ref "C36") (pin "1") (pinfunction "1_1") (pintype "passive"))
      (node (ref "R57") (pin "1") (pinfunction "1_1") (pintype "passive"))
      (node (ref "U5") (pin "1") (pinfunction "OUT_1") (pintype "output"))
    )
    (net (code "27") (name "PWRGND01") (class "Default")
      (node (ref "C37") (pin "2") (pinfunction "2_2") (pintype "passive"))
      (node (ref "C38") (pin "2") (pinfunction "2_2") (pintype "passive"))
      (node (ref "C65") (pin "2") (pinfunction "2_2") (pintype "passive"))
      (node (ref "C67") (pin "1") (pinfunction "1_1") (pintype "passive"))
      (node (ref "D10") (pin "2") (pinfunction "A_2") (pintype "passive"))
      (node (ref "Q8") (pin "2") (pinfunction "E_2") (pintype "passive"))
      (node (ref "R45") (pin "2") (pinfunction "2_2") (pintype "passive"))
      (node (ref "R53") (pin "1") (pinfunction "1_1") (pintype "passive"))
      (node (ref "R56") (pin "2") (pinfunction "2_2") (pintype "passive"))
      (node (ref "R58") (pin "2") (pinfunction "2_2") (pintype "passive"))
      (node (ref "TP8") (pin "1") (pintype "passive"))
      (node (ref "U5") (pin "2") (pinfunction "V-_2") (pintype "power_in"))
    )
    (net (code "28") (name "PWRGND11") (class "Default")
      (node (ref "C26") (pin "2") (pinfunction "2_2") (pintype "passive"))
      (node (ref "C27") (pin "2") (pinfunction "2_2") (pintype "passive"))
      (node (ref "C28") (pin "1") (pinfunction "+_1") (pintype "passive"))
      (node (ref "C32") (pin "1") (pinfunction "1_1") (pintype "passive"))
      (node (ref "C33") (pin "1") (pinfunction "1_1") (pintype "passive"))
      (node (ref "C34") (pin "2") (pinfunction "-_2") (pintype "passive"))
      (node (ref "J5") (pin "1") (pinfunction "1_1") (pintype "passive"))
      (node (ref "J6") (pin "2") (pinfunction "2_2") (pintype "passive"))
      (node (ref "R49") (pin "2") (pinfunction "2_2") (pintype "passive"))
      (node (ref "R53") (pin "2") (pinfunction "2_2") (pintype "passive"))
      (node (ref "T2") (pin "8") (pinfunction "8_8") (pintype "passive"))
    )
    (net (code "29") (name "VCONT1") (class "Default")
      (node (ref "R44") (pin "2") (pinfunction "2_2") (pintype "passive"))
      (node (ref "TP7") (pin "1") (pintype "passive"))
    )
    (net (code "30") (name "VOPAMP1") (class "Default")
      (node (ref "C37") (pin "1") (pinfunction "1_1") (pintype "passive"))
      (node (ref "C38") (pin "1") (pinfunction "1_1") (pintype "passive"))
      (node (ref "Q7") (pin "2") (pinfunction "E_2") (pintype "passive"))
      (node (ref "U5") (pin "5") (pinfunction "V+_5") (pintype "power_in"))
    )
    (net (code "31") (name "Vin") (class "Default")
      (node (ref "C23") (pin "1") (pinfunction "+_1") (pintype "passive"))
      (node (ref "C24") (pin "1") (pinfunction "1_1") (pintype "passive"))
      (node (ref "C25") (pin "1") (pinfunction "1_1") (pintype "passive"))
      (node (ref "C29") (pin "1") (pinfunction "1_1") (pintype "passive"))
      (node (ref "D8") (pin "1") (pinfunction "K_1") (pintype "passive"))
      (node (ref "J1") (pin "2") (pinfunction "2_2") (pintype "passive"))
      (node (ref "Q7") (pin "3") (pinfunction "C_3") (pintype "passive"))
      (node (ref "R31") (pin "2") (pinfunction "2_2") (pintype "passive"))
      (node (ref "R32") (pin "2") (pinfunction "2_2") (pintype "passive"))
      (node (ref "R33") (pin "2") (pinfunction "2_2") (pintype "passive"))
      (node (ref "R34") (pin "1") (pinfunction "1_1") (pintype "passive"))
      (node (ref "R35") (pin "2") (pinfunction "2_2") (pintype "passive"))
      (node (ref "R51") (pin "2") (pinfunction "2_2") (pintype "passive"))
      (node (ref "T2") (pin "2") (pinfunction "2_2") (pintype "passive"))
    )
    (net (code "32") (name "unconnected-(T2-NC-Pad1)") (class "Default")
      (node (ref "T2") (pin "1") (pinfunction "NC_1") (pintype "passive"))
    )
    (net (code "33") (name "unconnected-(T2-NC-Pad3)") (class "Default")
      (node (ref "T2") (pin "3") (pinfunction "NC_3") (pintype "passive"))
    )
    (net (code "34") (name "unconnected-(T2-NC-Pad5)") (class "Default")
      (node (ref "T2") (pin "5") (pinfunction "NC_5") (pintype "passive"))
    )
    (net (code "35") (name "unconnected-(T2-NC-Pad6)") (class "Default")
      (node (ref "T2") (pin "6") (pinfunction "NC_6") (pintype "passive"))
    )
    (net (code "36") (name "unconnected-(T2-NC-Pad10)") (class "Default")
      (node (ref "T2") (pin "10") (pinfunction "NC_10") (pintype "passive"))
    )
  )
)
